# RF.net
KiCad netlist of a schematic drawn in Altium Designer
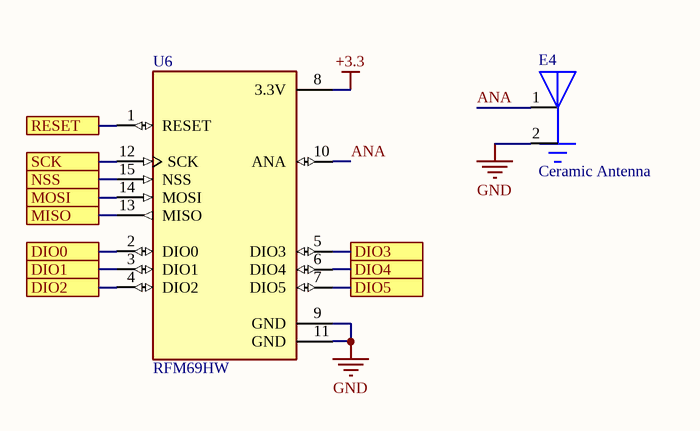
[diagram p0: RF.SchDoc]

(export (version "E")
  (design (tool "Eeschema 10.0.6"))
  (components
    (comp (ref "E4")
      (value "Ceramic Antenna")
      (footprint "Ceramic_915M")
      (libsource (lib "Antenna") (part "Ceramic Antenna"))
    )
    (comp (ref "U6") (value "RFM69HW") (footprint "RFM69HW") (libsource (lib "RF Module") (part "RFM69HW")))
  )
  (nets
    (net (code "1") (name "+3.3") (class "Default")
      (node (ref "U6") (pin "8") (pinfunction "3.3V_8") (pintype "power_in"))
    )
    (net (code "2") (name "/ANA") (class "Default")
      (node (ref "E4") (pin "1") (pinfunction "1_1") (pintype "passive"))
      (node (ref "U6") (pin "10") (pinfunction "ANA_10") (pintype "bidirectional"))
    )
    (net (code "3") (name "/DIO0") (class "Default")
      (node (ref "U6") (pin "2") (pinfunction "DIO0_2") (pintype "bidirectional"))
    )
    (net (code "4") (name "/DIO1") (class "Default")
      (node (ref "U6") (pin "3") (pinfunction "DIO1_3") (pintype "bidirectional"))
    )
    (net (code "5") (name "/DIO2") (class "Default")
      (node (ref "U6") (pin "4") (pinfunction "DIO2_4") (pintype "bidirectional"))
    )
    (net (code "6") (name "/DIO3") (class "Default")
      (node (ref "U6") (pin "5") (pinfunction "DIO3_5") (pintype "bidirectional"))
    )
    (net (code "7") (name "/DIO4") (class "Default")
      (node (ref "U6") (pin "6") (pinfunction "DIO4_6") (pintype "bidirectional"))
    )
    (net (code "8") (name "/DIO5") (class "Default")
      (node (ref "U6") (pin "7") (pinfunction "DIO5_7") (pintype "bidirectional"))
    )
    (net (code "9") (name "/MISO") (class "Default")
      (node (ref "U6") (pin "13") (pinfunction "MISO_13") (pintype "output"))
    )
    (net (code "10") (name "/MOSI") (class "Default")
      (node (ref "U6") (pin "14") (pinfunction "MOSI_14") (pintype "input"))
    )
    (net (code "11") (name "/NSS") (class "Default")
      (node (ref "U6") (pin "15") (pinfunction "NSS_15") (pintype "input"))
    )
    (net (code "12") (name "/RESET") (class "Default")
      (node (ref "U6") (pin "1") (pinfunction "RESET_1") (pintype "bidirectional"))
    )
    (net (code "13") (name "/SCK") (class "Default")
      (node (ref "U6") (pin "12") (pinfunction "SCK_12") (pintype "input"))
    )
    (net (code "14") (name "GND") (class "Default")
      (node (ref "E4") (pin "2") (pinfunction "2_2") (pintype "passive"))
      (node (ref "U6") (pin "11") (pinfunction "GND_11") (pintype "power_in"))
      (node (ref "U6") (pin "9") (pinfunction "GND_9") (pintype "power_in"))
    )
  )
)
